# Tah_Board_Ver_1_0.net
KiCad netlist of a schematic drawn in EAGLE
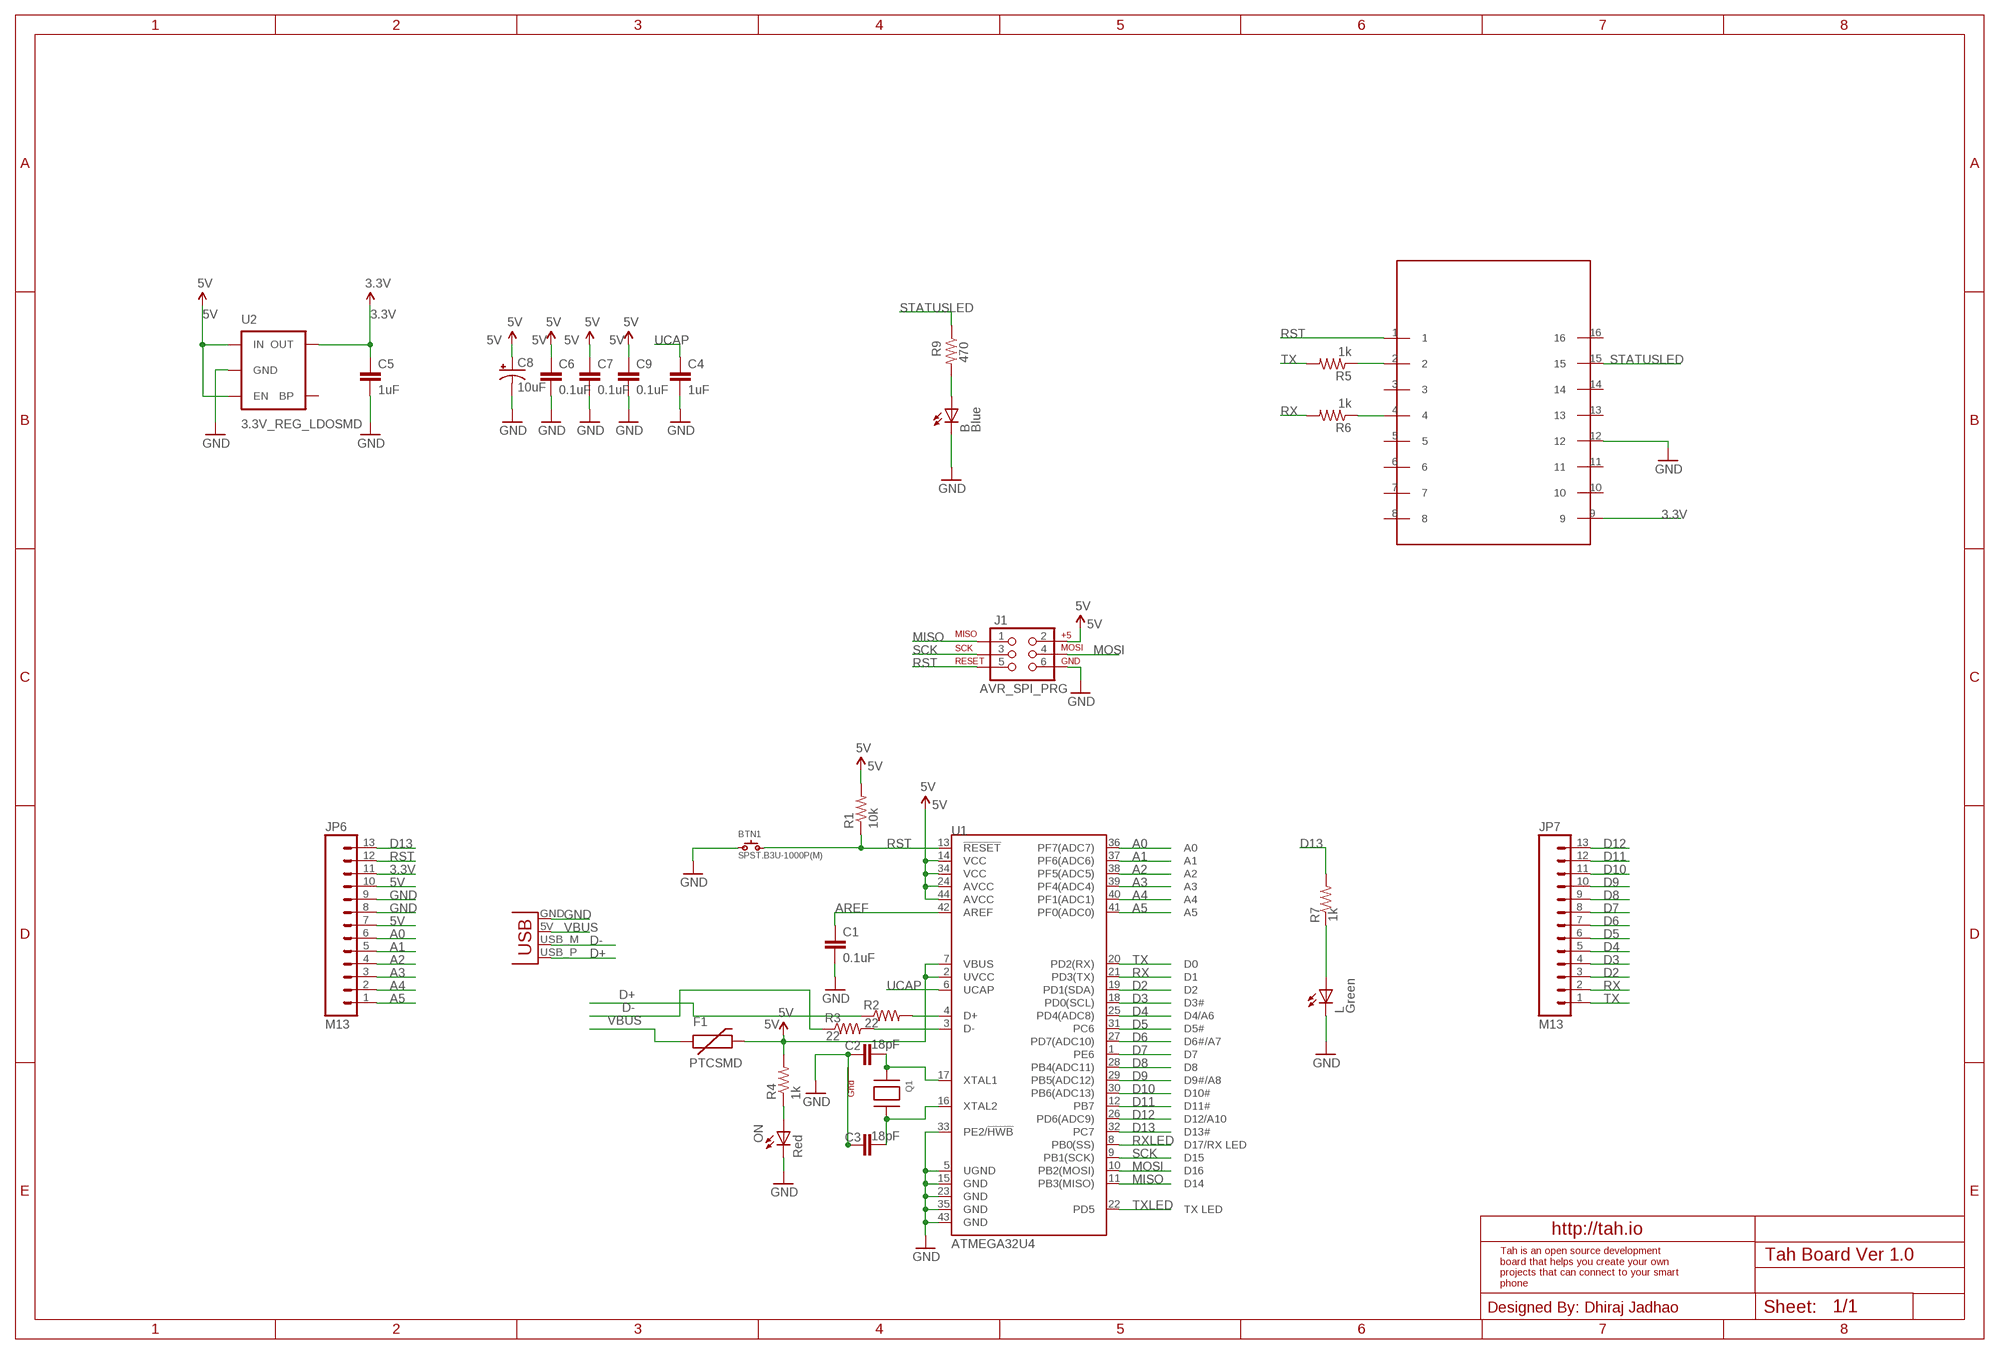
[diagram p0: schematic, sheet 1]

(export (version "E")
  (design (tool "Eeschema 10.0.6"))
  (components
    (comp (ref "B")
      (value "Blue")
      (footprint "eagle-import:1206")
      (libsource (lib "eagle-import") (part "LEDSMT1206"))
    )
    (comp (ref "BLE")
      (value "HM-11HM11")
      (footprint "eagle-import:BC05B-SMD")
      (libsource (lib "eagle-import") (part "HM-11HM11"))
    )
    (comp (ref "BTN1")
      (value "SPST.B3U-1000P(M)")
      (footprint "eagle-import:B3U-1000P(M)")
      (libsource (lib "eagle-import") (part "SPST.B3U-1000P(M)"))
    )
    (comp (ref "C1")
      (value "0.1uF")
      (footprint "eagle-import:1206")
      (libsource (lib "eagle-import") (part "2.2UF-CERCAP-10009"))
    )
    (comp (ref "C2")
      (value "18pF")
      (footprint "eagle-import:1206")
      (libsource (lib "eagle-import") (part "2.2UF-CERCAP-10009"))
    )
    (comp (ref "C3")
      (value "18pF")
      (footprint "eagle-import:1206")
      (libsource (lib "eagle-import") (part "2.2UF-CERCAP-10009"))
    )
    (comp (ref "C4")
      (value "1uF")
      (footprint "eagle-import:1206")
      (libsource (lib "eagle-import") (part "2.2UF-CERCAP-10009"))
    )
    (comp (ref "C5")
      (value "1uF")
      (footprint "eagle-import:1206")
      (libsource (lib "eagle-import") (part "2.2UF-CERCAP-10009"))
    )
    (comp (ref "C6")
      (value "0.1uF")
      (footprint "eagle-import:1206")
      (libsource (lib "eagle-import") (part "2.2UF-CERCAP-10009"))
    )
    (comp (ref "C7")
      (value "0.1uF")
      (footprint "eagle-import:1206")
      (libsource (lib "eagle-import") (part "2.2UF-CERCAP-10009"))
    )
    (comp (ref "C8")
      (value "10uF")
      (footprint "eagle-import:EIA3216")
      (libsource (lib "eagle-import") (part "CAP_POL1206"))
    )
    (comp (ref "C9")
      (value "0.1uF")
      (footprint "eagle-import:1206")
      (libsource (lib "eagle-import") (part "2.2UF-CERCAP-10009"))
    )
    (comp (ref "F1")
      (value "PTCSMD")
      (footprint "eagle-import:PTC-1206")
      (libsource (lib "eagle-import") (part "PTCSMD"))
    )
    (comp (ref "J1")
      (value "AVR_SPI_PRG")
      (footprint "eagle-import:2X3")
      (libsource (lib "eagle-import") (part "AVR_SPI_PRG_6PTH"))
    )
    (comp (ref "JP2")
      (value "USBPCB")
      (footprint "eagle-import:USB-A-PCB")
      (libsource (lib "eagle-import") (part "USBPCB"))
    )
    (comp (ref "JP6")
      (value "M13")
      (footprint "eagle-import:1X13")
      (libsource (lib "eagle-import") (part "M13"))
    )
    (comp (ref "JP7")
      (value "M13")
      (footprint "eagle-import:1X13")
      (libsource (lib "eagle-import") (part "M13"))
    )
    (comp (ref "L")
      (value "Green")
      (footprint "eagle-import:1206")
      (libsource (lib "eagle-import") (part "LEDSMT1206"))
    )
    (comp (ref "ON")
      (value "Red")
      (footprint "eagle-import:1206")
      (libsource (lib "eagle-import") (part "LEDSMT1206"))
    )
    (comp (ref "Q1")
      (value "XTAL-4-3225")
      (footprint "eagle-import:NX3225")
      (libsource (lib "eagle-import") (part "XTAL-4-3225"))
    )
    (comp (ref "R1")
      (value "10k")
      (footprint "eagle-import:1206")
      (libsource (lib "eagle-import") (part "RESISTOR1206"))
    )
    (comp (ref "R2")
      (value "22")
      (footprint "eagle-import:1206")
      (libsource (lib "eagle-import") (part "RESISTOR1206"))
    )
    (comp (ref "R3")
      (value "22")
      (footprint "eagle-import:1206")
      (libsource (lib "eagle-import") (part "RESISTOR1206"))
    )
    (comp (ref "R4")
      (value "1k")
      (footprint "eagle-import:1206")
      (libsource (lib "eagle-import") (part "RESISTOR1206"))
    )
    (comp (ref "R5")
      (value "1k")
      (footprint "eagle-import:1206")
      (libsource (lib "eagle-import") (part "RESISTOR1206"))
    )
    (comp (ref "R6")
      (value "1k")
      (footprint "eagle-import:1206")
      (libsource (lib "eagle-import") (part "RESISTOR1206"))
    )
    (comp (ref "R7")
      (value "1k")
      (footprint "eagle-import:1206")
      (libsource (lib "eagle-import") (part "RESISTOR1206"))
    )
    (comp (ref "R9")
      (value "470")
      (footprint "eagle-import:1206")
      (libsource (lib "eagle-import") (part "RESISTOR1206"))
    )
    (comp (ref "U1")
      (value "ATMEGA32U4")
      (footprint "eagle-import:SPARKFUN-DIGITALIC_QFN-44-NOPAD")
      (libsource (lib "eagle-import") (part "ATMEGA32U4QFN2"))
    )
    (comp (ref "U2")
      (value "3.3V_REG_LDOSMD")
      (footprint "eagle-import:SOT23-5")
      (libsource (lib "eagle-import") (part "V_REG_LDOSMD"))
    )
  )
  (nets
    (net (code "1") (name "/A0") (class "Default")
      (node (ref "JP6") (pin "6") (pinfunction "6_6") (pintype "passive"))
      (node (ref "U1") (pin "36") (pinfunction "PF7(ADC7)_36") (pintype "bidirectional"))
    )
    (net (code "2") (name "/A1") (class "Default")
      (node (ref "JP6") (pin "5") (pinfunction "5_5") (pintype "passive"))
      (node (ref "U1") (pin "37") (pinfunction "PF6(ADC6)_37") (pintype "bidirectional"))
    )
    (net (code "3") (name "/A2") (class "Default")
      (node (ref "JP6") (pin "4") (pinfunction "4_4") (pintype "passive"))
      (node (ref "U1") (pin "38") (pinfunction "PF5(ADC5)_38") (pintype "bidirectional"))
    )
    (net (code "4") (name "/A3") (class "Default")
      (node (ref "JP6") (pin "3") (pinfunction "3_3") (pintype "passive"))
      (node (ref "U1") (pin "39") (pinfunction "PF4(ADC4)_39") (pintype "bidirectional"))
    )
    (net (code "5") (name "/A4") (class "Default")
      (node (ref "JP6") (pin "2") (pinfunction "2_2") (pintype "passive"))
      (node (ref "U1") (pin "40") (pinfunction "PF1(ADC1)_40") (pintype "bidirectional"))
    )
    (net (code "6") (name "/A5") (class "Default")
      (node (ref "JP6") (pin "1") (pinfunction "1_1") (pintype "passive"))
      (node (ref "U1") (pin "41") (pinfunction "PF0(ADC0)_41") (pintype "bidirectional"))
    )
    (net (code "7") (name "/AREF") (class "Default")
      (node (ref "C1") (pin "1") (pinfunction "1_1") (pintype "passive"))
      (node (ref "U1") (pin "42") (pinfunction "AREF_42") (pintype "bidirectional"))
    )
    (net (code "8") (name "/D+") (class "Default")
      (node (ref "JP2") (pin "USB_P") (pinfunction "D+_USB_P") (pintype "bidirectional"))
      (node (ref "R2") (pin "1") (pinfunction "1_1") (pintype "passive"))
    )
    (net (code "9") (name "/D-") (class "Default")
      (node (ref "JP2") (pin "USB_M") (pinfunction "D-_USB_M") (pintype "bidirectional"))
      (node (ref "R3") (pin "1") (pinfunction "1_1") (pintype "passive"))
    )
    (net (code "10") (name "/D2") (class "Default")
      (node (ref "JP7") (pin "3") (pinfunction "3_3") (pintype "passive"))
      (node (ref "U1") (pin "19") (pinfunction "PD1(SDA)_19") (pintype "bidirectional"))
    )
    (net (code "11") (name "/D3") (class "Default")
      (node (ref "JP7") (pin "4") (pinfunction "4_4") (pintype "passive"))
      (node (ref "U1") (pin "18") (pinfunction "PD0(SCL)_18") (pintype "bidirectional"))
    )
    (net (code "12") (name "/D4") (class "Default")
      (node (ref "JP7") (pin "5") (pinfunction "5_5") (pintype "passive"))
      (node (ref "U1") (pin "25") (pinfunction "PD4(ADC8)_25") (pintype "bidirectional"))
    )
    (net (code "13") (name "/D5") (class "Default")
      (node (ref "JP7") (pin "6") (pinfunction "6_6") (pintype "passive"))
      (node (ref "U1") (pin "31") (pinfunction "PC6_31") (pintype "bidirectional"))
    )
    (net (code "14") (name "/D6") (class "Default")
      (node (ref "JP7") (pin "7") (pinfunction "7_7") (pintype "passive"))
      (node (ref "U1") (pin "27") (pinfunction "PD7(ADC10)_27") (pintype "bidirectional"))
    )
    (net (code "15") (name "/D7") (class "Default")
      (node (ref "JP7") (pin "8") (pinfunction "8_8") (pintype "passive"))
      (node (ref "U1") (pin "1") (pinfunction "PE6_1") (pintype "bidirectional"))
    )
    (net (code "16") (name "/D8") (class "Default")
      (node (ref "JP7") (pin "9") (pinfunction "9_9") (pintype "passive"))
      (node (ref "U1") (pin "28") (pinfunction "PB4(ADC11)_28") (pintype "bidirectional"))
    )
    (net (code "17") (name "/D9") (class "Default")
      (node (ref "JP7") (pin "10") (pinfunction "10_10") (pintype "passive"))
      (node (ref "U1") (pin "29") (pinfunction "PB5(ADC12)_29") (pintype "bidirectional"))
    )
    (net (code "18") (name "/D10") (class "Default")
      (node (ref "JP7") (pin "11") (pinfunction "11_11") (pintype "passive"))
      (node (ref "U1") (pin "30") (pinfunction "PB6(ADC13)_30") (pintype "bidirectional"))
    )
    (net (code "19") (name "/D11") (class "Default")
      (node (ref "JP7") (pin "12") (pinfunction "12_12") (pintype "passive"))
      (node (ref "U1") (pin "12") (pinfunction "PB7_12") (pintype "bidirectional"))
    )
    (net (code "20") (name "/D12") (class "Default")
      (node (ref "JP7") (pin "13") (pinfunction "13_13") (pintype "passive"))
      (node (ref "U1") (pin "26") (pinfunction "PD6(ADC9)_26") (pintype "bidirectional"))
    )
    (net (code "21") (name "/D13") (class "Default")
      (node (ref "JP6") (pin "13") (pinfunction "13_13") (pintype "passive"))
      (node (ref "R7") (pin "2") (pinfunction "2_2") (pintype "passive"))
      (node (ref "U1") (pin "32") (pinfunction "PC7_32") (pintype "bidirectional"))
    )
    (net (code "22") (name "/MISO") (class "Default")
      (node (ref "J1") (pin "1") (pinfunction "1_1") (pintype "passive"))
      (node (ref "U1") (pin "11") (pinfunction "PB3(MISO)_11") (pintype "bidirectional"))
    )
    (net (code "23") (name "/MOSI") (class "Default")
      (node (ref "J1") (pin "4") (pinfunction "4_4") (pintype "passive"))
      (node (ref "U1") (pin "10") (pinfunction "PB2(MOSI)_10") (pintype "bidirectional"))
    )
    (net (code "24") (name "/RST") (class "Default")
      (node (ref "BLE") (pin "1") (pinfunction "1_1") (pintype "bidirectional"))
      (node (ref "BTN1") (pin "2") (pinfunction "2_2") (pintype "bidirectional"))
      (node (ref "J1") (pin "5") (pinfunction "5_5") (pintype "passive"))
      (node (ref "JP6") (pin "12") (pinfunction "12_12") (pintype "passive"))
      (node (ref "R1") (pin "1") (pinfunction "1_1") (pintype "passive"))
      (node (ref "U1") (pin "13") (pinfunction "~{RESET}_13") (pintype "bidirectional"))
    )
    (net (code "25") (name "/RX") (class "Default")
      (node (ref "JP7") (pin "2") (pinfunction "2_2") (pintype "passive"))
      (node (ref "R6") (pin "2") (pinfunction "2_2") (pintype "passive"))
      (node (ref "U1") (pin "21") (pinfunction "PD3(TX)_21") (pintype "bidirectional"))
    )
    (net (code "26") (name "/RXLED") (class "Default")
      (node (ref "U1") (pin "8") (pinfunction "PB0(SS)_8") (pintype "bidirectional"))
    )
    (net (code "27") (name "/SCK") (class "Default")
      (node (ref "J1") (pin "3") (pinfunction "3_3") (pintype "passive"))
      (node (ref "U1") (pin "9") (pinfunction "PB1(SCK)_9") (pintype "bidirectional"))
    )
    (net (code "28") (name "/STATUSLED") (class "Default")
      (node (ref "BLE") (pin "15") (pinfunction "15_15") (pintype "bidirectional"))
      (node (ref "R9") (pin "1") (pinfunction "1_1") (pintype "passive"))
    )
    (net (code "29") (name "/TX") (class "Default")
      (node (ref "JP7") (pin "1") (pinfunction "1_1") (pintype "passive"))
      (node (ref "R5") (pin "2") (pinfunction "2_2") (pintype "passive"))
      (node (ref "U1") (pin "20") (pinfunction "PD2(RX)_20") (pintype "bidirectional"))
    )
    (net (code "30") (name "/TXLED") (class "Default")
      (node (ref "U1") (pin "22") (pinfunction "PD5_22") (pintype "bidirectional"))
    )
    (net (code "31") (name "/UCAP") (class "Default")
      (node (ref "C4") (pin "1") (pinfunction "1_1") (pintype "passive"))
      (node (ref "U1") (pin "6") (pinfunction "UCAP_6") (pintype "bidirectional"))
    )
    (net (code "32") (name "/VBUS") (class "Default")
      (node (ref "F1") (pin "1") (pinfunction "1_1") (pintype "bidirectional"))
      (node (ref "JP2") (pin "5V") (pinfunction "VBUS_5V") (pintype "bidirectional"))
    )
    (net (code "33") (name "3.3V") (class "Default")
      (node (ref "BLE") (pin "9") (pinfunction "9_9") (pintype "bidirectional"))
      (node (ref "C5") (pin "1") (pinfunction "1_1") (pintype "passive"))
      (node (ref "JP6") (pin "11") (pinfunction "11_11") (pintype "passive"))
      (node (ref "U2") (pin "5") (pinfunction "OUT_5") (pintype "passive"))
    )
    (net (code "34") (name "5V") (class "Default")
      (node (ref "C6") (pin "1") (pinfunction "1_1") (pintype "passive"))
      (node (ref "C7") (pin "1") (pinfunction "1_1") (pintype "passive"))
      (node (ref "C8") (pin "A") (pinfunction "+_A") (pintype "passive"))
      (node (ref "C9") (pin "1") (pinfunction "1_1") (pintype "passive"))
      (node (ref "F1") (pin "2") (pinfunction "2_2") (pintype "bidirectional"))
      (node (ref "J1") (pin "2") (pinfunction "2_2") (pintype "passive"))
      (node (ref "JP6") (pin "10") (pinfunction "10_10") (pintype "passive"))
      (node (ref "JP6") (pin "7") (pinfunction "7_7") (pintype "passive"))
      (node (ref "R1") (pin "2") (pinfunction "2_2") (pintype "passive"))
      (node (ref "R4") (pin "2") (pinfunction "2_2") (pintype "passive"))
      (node (ref "U1") (pin "14") (pinfunction "VCC_14") (pintype "bidirectional"))
      (node (ref "U1") (pin "2") (pinfunction "UVCC_2") (pintype "bidirectional"))
      (node (ref "U1") (pin "24") (pinfunction "AVCC_24") (pintype "bidirectional"))
      (node (ref "U1") (pin "34") (pinfunction "VCC_34") (pintype "bidirectional"))
      (node (ref "U1") (pin "44") (pinfunction "AVCC_44") (pintype "bidirectional"))
      (node (ref "U1") (pin "7") (pinfunction "VBUS_7") (pintype "bidirectional"))
      (node (ref "U2") (pin "1") (pinfunction "IN_1") (pintype "input"))
      (node (ref "U2") (pin "3") (pinfunction "EN_3") (pintype "input"))
    )
    (net (code "35") (name "GND") (class "Default")
      (node (ref "B") (pin "C") (pinfunction "C_C") (pintype "passive"))
      (node (ref "BLE") (pin "12") (pinfunction "12_12") (pintype "bidirectional"))
      (node (ref "BTN1") (pin "1") (pinfunction "1_1") (pintype "bidirectional"))
      (node (ref "C1") (pin "2") (pinfunction "2_2") (pintype "passive"))
      (node (ref "C2") (pin "1") (pinfunction "1_1") (pintype "passive"))
      (node (ref "C3") (pin "1") (pinfunction "1_1") (pintype "passive"))
      (node (ref "C4") (pin "2") (pinfunction "2_2") (pintype "passive"))
      (node (ref "C5") (pin "2") (pinfunction "2_2") (pintype "passive"))
      (node (ref "C6") (pin "2") (pinfunction "2_2") (pintype "passive"))
      (node (ref "C7") (pin "2") (pinfunction "2_2") (pintype "passive"))
      (node (ref "C8") (pin "C") (pinfunction "-_C") (pintype "passive"))
      (node (ref "C9") (pin "2") (pinfunction "2_2") (pintype "passive"))
      (node (ref "J1") (pin "6") (pinfunction "6_6") (pintype "passive"))
      (node (ref "JP2") (pin "GND") (pinfunction "GND_GND") (pintype "bidirectional"))
      (node (ref "JP6") (pin "8") (pinfunction "8_8") (pintype "passive"))
      (node (ref "JP6") (pin "9") (pinfunction "9_9") (pintype "passive"))
      (node (ref "L") (pin "C") (pinfunction "C_C") (pintype "passive"))
      (node (ref "ON") (pin "C") (pinfunction "C_C") (pintype "passive"))
      (node (ref "Q1") (pin "2") (pinfunction "G2_2") (pintype "power_in"))
      (node (ref "Q1") (pin "4") (pinfunction "G1_4") (pintype "power_in"))
      (node (ref "U1") (pin "15") (pinfunction "GND_15") (pintype "bidirectional"))
      (node (ref "U1") (pin "23") (pinfunction "GND_23") (pintype "bidirectional"))
      (node (ref "U1") (pin "33") (pinfunction "PE2/~{HWB}_33") (pintype "bidirectional"))
      (node (ref "U1") (pin "35") (pinfunction "GND_35") (pintype "bidirectional"))
      (node (ref "U1") (pin "43") (pinfunction "GND_43") (pintype "bidirectional"))
      (node (ref "U1") (pin "5") (pinfunction "UGND_5") (pintype "bidirectional"))
      (node (ref "U2") (pin "2") (pinfunction "GND_2") (pintype "input"))
    )
    (net (code "36") (name "Net-(B-PadA)") (class "Default")
      (node (ref "B") (pin "A") (pinfunction "A_A") (pintype "passive"))
      (node (ref "R9") (pin "2") (pinfunction "2_2") (pintype "passive"))
    )
    (net (code "37") (name "Net-(BLE-Pad2)") (class "Default")
      (node (ref "BLE") (pin "2") (pinfunction "2_2") (pintype "bidirectional"))
      (node (ref "R5") (pin "1") (pinfunction "1_1") (pintype "passive"))
    )
    (net (code "38") (name "Net-(BLE-Pad4)") (class "Default")
      (node (ref "BLE") (pin "4") (pinfunction "4_4") (pintype "bidirectional"))
      (node (ref "R6") (pin "1") (pinfunction "1_1") (pintype "passive"))
    )
    (net (code "39") (name "Net-(L-PadA)") (class "Default")
      (node (ref "L") (pin "A") (pinfunction "A_A") (pintype "passive"))
      (node (ref "R7") (pin "1") (pinfunction "1_1") (pintype "passive"))
    )
    (net (code "40") (name "Net-(ON-PadA)") (class "Default")
      (node (ref "ON") (pin "A") (pinfunction "A_A") (pintype "passive"))
      (node (ref "R4") (pin "1") (pinfunction "1_1") (pintype "passive"))
    )
    (net (code "41") (name "Net-(Q1-X1)") (class "Default")
      (node (ref "C2") (pin "2") (pinfunction "2_2") (pintype "passive"))
      (node (ref "Q1") (pin "1") (pinfunction "X1_1") (pintype "bidirectional"))
      (node (ref "U1") (pin "17") (pinfunction "XTAL1_17") (pintype "bidirectional"))
    )
    (net (code "42") (name "Net-(Q1-X2)") (class "Default")
      (node (ref "C3") (pin "2") (pinfunction "2_2") (pintype "passive"))
      (node (ref "Q1") (pin "3") (pinfunction "X2_3") (pintype "bidirectional"))
      (node (ref "U1") (pin "16") (pinfunction "XTAL2_16") (pintype "bidirectional"))
    )
    (net (code "43") (name "Net-(U1-D+)") (class "Default")
      (node (ref "R2") (pin "2") (pinfunction "2_2") (pintype "passive"))
      (node (ref "U1") (pin "4") (pinfunction "D+_4") (pintype "bidirectional"))
    )
    (net (code "44") (name "Net-(U1-D-)") (class "Default")
      (node (ref "R3") (pin "2") (pinfunction "2_2") (pintype "passive"))
      (node (ref "U1") (pin "3") (pinfunction "D-_3") (pintype "bidirectional"))
    )
    (net (code "45") (name "unconnected-(BLE-Pad3)") (class "Default")
      (node (ref "BLE") (pin "3") (pinfunction "3_3") (pintype "bidirectional"))
    )
    (net (code "46") (name "unconnected-(BLE-Pad5)") (class "Default")
      (node (ref "BLE") (pin "5") (pinfunction "5_5") (pintype "bidirectional"))
    )
    (net (code "47") (name "unconnected-(BLE-Pad6)") (class "Default")
      (node (ref "BLE") (pin "6") (pinfunction "6_6") (pintype "bidirectional"))
    )
    (net (code "48") (name "unconnected-(BLE-Pad7)") (class "Default")
      (node (ref "BLE") (pin "7") (pinfunction "7_7") (pintype "bidirectional"))
    )
    (net (code "49") (name "unconnected-(BLE-Pad8)") (class "Default")
      (node (ref "BLE") (pin "8") (pinfunction "8_8") (pintype "bidirectional"))
    )
    (net (code "50") (name "unconnected-(BLE-Pad10)") (class "Default")
      (node (ref "BLE") (pin "10") (pinfunction "10_10") (pintype "bidirectional"))
    )
    (net (code "51") (name "unconnected-(BLE-Pad11)") (class "Default")
      (node (ref "BLE") (pin "11") (pinfunction "11_11") (pintype "bidirectional"))
    )
    (net (code "52") (name "unconnected-(BLE-Pad13)") (class "Default")
      (node (ref "BLE") (pin "13") (pinfunction "13_13") (pintype "bidirectional"))
    )
    (net (code "53") (name "unconnected-(BLE-Pad14)") (class "Default")
      (node (ref "BLE") (pin "14") (pinfunction "14_14") (pintype "bidirectional"))
    )
    (net (code "54") (name "unconnected-(BLE-Pad16)") (class "Default")
      (node (ref "BLE") (pin "16") (pinfunction "16_16") (pintype "bidirectional"))
    )
    (net (code "55") (name "unconnected-(U2-BP-Pad4)") (class "Default")
      (node (ref "U2") (pin "4") (pinfunction "BP_4") (pintype "input"))
    )
  )
)
